# LM335_LTC.net
KiCad netlist of a schematic drawn in EAGLE
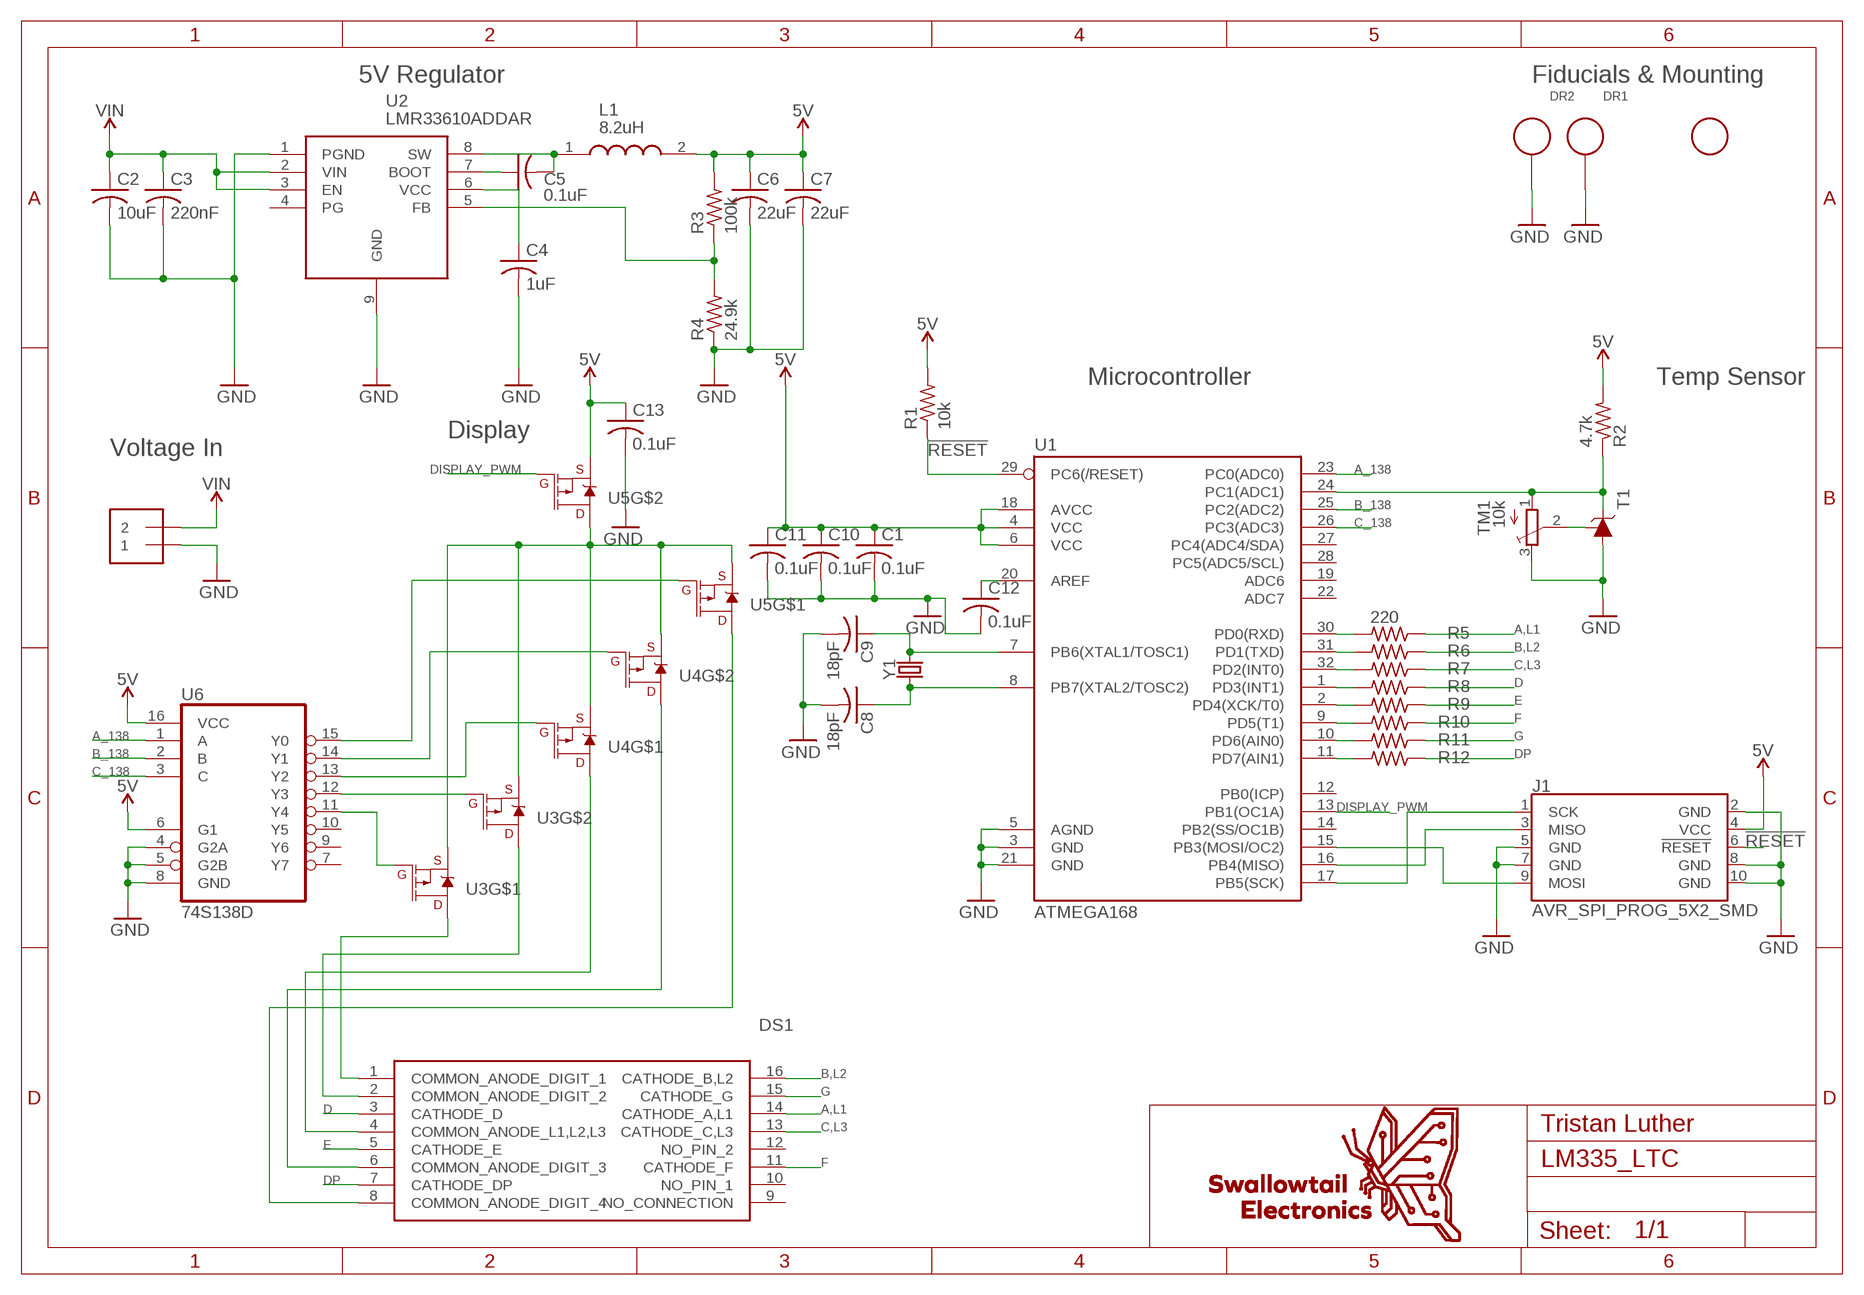
[diagram p0: schematic, sheet 1]

(export (version "E")
  (design (tool "Eeschema 10.0.6"))
  (components
    (comp (ref "C1")
      (value "0.1uF")
      (footprint "eagle-import:C0805")
      (libsource (lib "eagle-import") (part "C-USC0805"))
    )
    (comp (ref "C2")
      (value "10uF")
      (footprint "eagle-import:C0805")
      (libsource (lib "eagle-import") (part "C-USC0805"))
    )
    (comp (ref "C3")
      (value "220nF")
      (footprint "eagle-import:C0805")
      (libsource (lib "eagle-import") (part "C-USC0805"))
    )
    (comp (ref "C4")
      (value "1uF")
      (footprint "eagle-import:C0805")
      (libsource (lib "eagle-import") (part "C-USC0805"))
    )
    (comp (ref "C5")
      (value "0.1uF")
      (footprint "eagle-import:C0805")
      (libsource (lib "eagle-import") (part "C-USC0805"))
    )
    (comp (ref "C6")
      (value "22uF")
      (footprint "eagle-import:C0805")
      (libsource (lib "eagle-import") (part "C-USC0805"))
    )
    (comp (ref "C7")
      (value "22uF")
      (footprint "eagle-import:C0805")
      (libsource (lib "eagle-import") (part "C-USC0805"))
    )
    (comp (ref "C8")
      (value "18pF")
      (footprint "eagle-import:C0805")
      (libsource (lib "eagle-import") (part "C-USC0805"))
    )
    (comp (ref "C9")
      (value "18pF")
      (footprint "eagle-import:C0805")
      (libsource (lib "eagle-import") (part "C-USC0805"))
    )
    (comp (ref "C10")
      (value "0.1uF")
      (footprint "eagle-import:C0805")
      (libsource (lib "eagle-import") (part "C-USC0805"))
    )
    (comp (ref "C11")
      (value "0.1uF")
      (footprint "eagle-import:C0805")
      (libsource (lib "eagle-import") (part "C-USC0805"))
    )
    (comp (ref "C12")
      (value "0.1uF")
      (footprint "eagle-import:C0805")
      (libsource (lib "eagle-import") (part "C-USC0805"))
    )
    (comp (ref "C13")
      (value "0.1uF")
      (footprint "eagle-import:C0805")
      (libsource (lib "eagle-import") (part "C-USC0805"))
    )
    (comp (ref "DR1")
      (value "3MM_DRILL_GND")
      (footprint "eagle-import:3MM_DRILL_GND")
      (libsource (lib "eagle-import") (part "3MM_DRILL_GND"))
    )
    (comp (ref "DR2")
      (value "3MM_DRILL_GND")
      (footprint "eagle-import:3MM_DRILL_GND")
      (libsource (lib "eagle-import") (part "3MM_DRILL_GND"))
    )
    (comp (ref "DS1")
      (value "LTC-4627WC")
      (footprint "eagle-import:DIPS1016W50P254L4018H725Q16N")
      (fields (field (name "MOUSER_PART_NUMBER") "859-LTC-4627WC"))
      (libsource (lib "eagle-import") (part "LTC-4627WC"))
    )
    (comp (ref "J1")
      (value "AVR_SPI_PROG_5X2_SMD")
      (footprint "eagle-import:SAMTECH_FTSH-105-01")
      (libsource (lib "eagle-import") (part "AVR_SPI_PROG_5X2_SMD"))
    )
    (comp (ref "L1")
      (value "8.2uH")
      (footprint "eagle-import:INDPM5752X150N")
      (fields
        (field (name "ARROW_PART_NUMBER") "SRP5015TA-2R2M")
        (field (name "MOUSER_PART_NUMBER") "652-SRP5015TA-2R2M")
      )
      (libsource (lib "eagle-import") (part "SRP5015TA-2R2M"))
    )
    (comp (ref "R1")
      (value "10k")
      (footprint "eagle-import:R0805")
      (libsource (lib "eagle-import") (part "R-US_R0805"))
    )
    (comp (ref "R2")
      (value "4.7k")
      (footprint "eagle-import:R0805")
      (libsource (lib "eagle-import") (part "R-US_R0805"))
    )
    (comp (ref "R3")
      (value "100k")
      (footprint "eagle-import:R0805")
      (libsource (lib "eagle-import") (part "R-US_R0805"))
    )
    (comp (ref "R4")
      (value "24.9k")
      (footprint "eagle-import:R0805")
      (libsource (lib "eagle-import") (part "R-US_R0805"))
    )
    (comp (ref "R5")
      (value "220")
      (footprint "eagle-import:R0805")
      (libsource (lib "eagle-import") (part "R-US_R0805"))
    )
    (comp (ref "R6")
      (value "220")
      (footprint "eagle-import:R0805")
      (libsource (lib "eagle-import") (part "R-US_R0805"))
    )
    (comp (ref "R7")
      (value "220")
      (footprint "eagle-import:R0805")
      (libsource (lib "eagle-import") (part "R-US_R0805"))
    )
    (comp (ref "R8")
      (value "220")
      (footprint "eagle-import:R0805")
      (libsource (lib "eagle-import") (part "R-US_R0805"))
    )
    (comp (ref "R9")
      (value "220")
      (footprint "eagle-import:R0805")
      (libsource (lib "eagle-import") (part "R-US_R0805"))
    )
    (comp (ref "R10")
      (value "220")
      (footprint "eagle-import:R0805")
      (libsource (lib "eagle-import") (part "R-US_R0805"))
    )
    (comp (ref "R11")
      (value "220")
      (footprint "eagle-import:R0805")
      (libsource (lib "eagle-import") (part "R-US_R0805"))
    )
    (comp (ref "R12")
      (value "220")
      (footprint "eagle-import:R0805")
      (libsource (lib "eagle-import") (part "R-US_R0805"))
    )
    (comp (ref "T1")
      (value "LM335")
      (footprint "eagle-import:TO92")
      (libsource (lib "eagle-import") (part "LM335"))
    )
    (comp (ref "TM1")
      (value "10k")
      (footprint "eagle-import:TC33X")
      (libsource (lib "eagle-import") (part "TRIMPOTTC33X"))
    )
    (comp (ref "U$2")
      (value "25-B200-02")
      (footprint "eagle-import:25−B200-02")
      (libsource (lib "eagle-import") (part "25-B200-02"))
    )
    (comp (ref "U$4")
      (value "FIDUCIAL")
      (footprint "eagle-import:FIDUCIAL_1MM")
      (libsource (lib "eagle-import") (part "FIDUCIAL"))
    )
    (comp (ref "U1")
      (value "ATMEGA168")
      (footprint "eagle-import:TQFP32-08")
      (libsource (lib "eagle-import") (part "ATMEGA168"))
    )
    (comp (ref "U2")
      (value "LMR33610ADDAR")
      (footprint "eagle-import:SOIC127P600X170-9N")
      (fields
        (field (name "ARROW_PART_NUMBER") "LMR33630ADDAR")
        (field (name "MOUSER_PART_NUMBER") "595-LMR33630ADDAR")
      )
      (libsource (lib "eagle-import") (part "LMR33610ADDAR"))
    )
    (comp (ref "U3")
      (value "SI1967DH-T1-E3")
      (footprint "eagle-import:SOT363_PHILIPS")
      (libsource (lib "eagle-import") (part "SI1967DH-T1-E3"))
    )
    (comp (ref "U4")
      (value "SI1967DH-T1-E3")
      (footprint "eagle-import:SOT363_PHILIPS")
      (libsource (lib "eagle-import") (part "SI1967DH-T1-E3"))
    )
    (comp (ref "U5")
      (value "SI1967DH-T1-E3")
      (footprint "eagle-import:SOT363_PHILIPS")
      (libsource (lib "eagle-import") (part "SI1967DH-T1-E3"))
    )
    (comp (ref "U6")
      (value "74S138D")
      (footprint "eagle-import:SO16")
      (libsource (lib "eagle-import") (part "74138DS"))
    )
    (comp (ref "Y1")
      (value "16MHz")
      (footprint "eagle-import:CRYSTAL-SMD-5X3.2-4PAD")
      (libsource (lib "eagle-import") (part "CRYSTAL-16MHZSMD-5X3.2"))
    )
  )
  (nets
    (net (code "1") (name "/A,L1") (class "Default")
      (node (ref "DS1") (pin "14") (pinfunction "CATHODE_A,L1_14") (pintype "bidirectional"))
      (node (ref "R5") (pin "1") (pinfunction "1_1") (pintype "passive"))
    )
    (net (code "2") (name "/A_138") (class "Default")
      (node (ref "U1") (pin "23") (pinfunction "PC0(ADC0)_23") (pintype "bidirectional"))
      (node (ref "U6") (pin "1") (pinfunction "A_1") (pintype "input"))
    )
    (net (code "3") (name "/B,L2") (class "Default")
      (node (ref "DS1") (pin "16") (pinfunction "CATHODE_B,L2_16") (pintype "bidirectional"))
      (node (ref "R6") (pin "1") (pinfunction "1_1") (pintype "passive"))
    )
    (net (code "4") (name "/B_138") (class "Default")
      (node (ref "U1") (pin "25") (pinfunction "PC2(ADC2)_25") (pintype "bidirectional"))
      (node (ref "U6") (pin "2") (pinfunction "B_2") (pintype "input"))
    )
    (net (code "5") (name "/C,L3") (class "Default")
      (node (ref "DS1") (pin "13") (pinfunction "CATHODE_C,L3_13") (pintype "bidirectional"))
      (node (ref "R7") (pin "1") (pinfunction "1_1") (pintype "passive"))
    )
    (net (code "6") (name "/C_138") (class "Default")
      (node (ref "U1") (pin "26") (pinfunction "PC3(ADC3)_26") (pintype "bidirectional"))
      (node (ref "U6") (pin "3") (pinfunction "C_3") (pintype "input"))
    )
    (net (code "7") (name "/D") (class "Default")
      (node (ref "DS1") (pin "3") (pinfunction "CATHODE_D_3") (pintype "bidirectional"))
      (node (ref "R8") (pin "1") (pinfunction "1_1") (pintype "passive"))
    )
    (net (code "8") (name "/DISPLAY_PWM") (class "Default")
      (node (ref "U1") (pin "13") (pinfunction "PB1(OC1A)_13") (pintype "bidirectional"))
      (node (ref "U5") (pin "5") (pinfunction "G_5") (pintype "bidirectional"))
    )
    (net (code "9") (name "/DP") (class "Default")
      (node (ref "DS1") (pin "7") (pinfunction "CATHODE_DP_7") (pintype "bidirectional"))
      (node (ref "R12") (pin "1") (pinfunction "1_1") (pintype "passive"))
    )
    (net (code "10") (name "/E") (class "Default")
      (node (ref "DS1") (pin "5") (pinfunction "CATHODE_E_5") (pintype "bidirectional"))
      (node (ref "R9") (pin "1") (pinfunction "1_1") (pintype "passive"))
    )
    (net (code "11") (name "/F") (class "Default")
      (node (ref "DS1") (pin "11") (pinfunction "CATHODE_F_11") (pintype "bidirectional"))
      (node (ref "R10") (pin "1") (pinfunction "1_1") (pintype "passive"))
    )
    (net (code "12") (name "/G") (class "Default")
      (node (ref "DS1") (pin "15") (pinfunction "CATHODE_G_15") (pintype "bidirectional"))
      (node (ref "R11") (pin "1") (pinfunction "1_1") (pintype "passive"))
    )
    (net (code "13") (name "/~{RESET}") (class "Default")
      (node (ref "J1") (pin "6") (pinfunction "~{RESET}_6") (pintype "bidirectional"))
      (node (ref "R1") (pin "1") (pinfunction "1_1") (pintype "passive"))
      (node (ref "U1") (pin "29") (pinfunction "PC6(/RESET)_29") (pintype "bidirectional"))
    )
    (net (code "14") (name "5V") (class "Default")
      (node (ref "C1") (pin "1") (pinfunction "1_1") (pintype "passive"))
      (node (ref "C10") (pin "1") (pinfunction "1_1") (pintype "passive"))
      (node (ref "C11") (pin "1") (pinfunction "1_1") (pintype "passive"))
      (node (ref "C13") (pin "1") (pinfunction "1_1") (pintype "passive"))
      (node (ref "C6") (pin "1") (pinfunction "1_1") (pintype "passive"))
      (node (ref "C7") (pin "1") (pinfunction "1_1") (pintype "passive"))
      (node (ref "J1") (pin "4") (pinfunction "VCC_4") (pintype "bidirectional"))
      (node (ref "L1") (pin "2") (pinfunction "2_2") (pintype "bidirectional"))
      (node (ref "R1") (pin "2") (pinfunction "2_2") (pintype "passive"))
      (node (ref "R2") (pin "2") (pinfunction "2_2") (pintype "passive"))
      (node (ref "R3") (pin "2") (pinfunction "2_2") (pintype "passive"))
      (node (ref "U1") (pin "18") (pinfunction "AVCC_18") (pintype "bidirectional"))
      (node (ref "U1") (pin "4") (pinfunction "VCC_4") (pintype "bidirectional"))
      (node (ref "U1") (pin "6") (pinfunction "VCC_6") (pintype "bidirectional"))
      (node (ref "U5") (pin "4") (pinfunction "S_4") (pintype "bidirectional"))
      (node (ref "U6") (pin "16") (pinfunction "VCC_16") (pintype "power_in"))
      (node (ref "U6") (pin "6") (pinfunction "G1_6") (pintype "input"))
    )
    (net (code "15") (name "GND") (class "Default")
      (node (ref "C1") (pin "2") (pinfunction "2_2") (pintype "passive"))
      (node (ref "C10") (pin "2") (pinfunction "2_2") (pintype "passive"))
      (node (ref "C11") (pin "2") (pinfunction "2_2") (pintype "passive"))
      (node (ref "C12") (pin "2") (pinfunction "2_2") (pintype "passive"))
      (node (ref "C13") (pin "2") (pinfunction "2_2") (pintype "passive"))
      (node (ref "C2") (pin "2") (pinfunction "2_2") (pintype "passive"))
      (node (ref "C3") (pin "2") (pinfunction "2_2") (pintype "passive"))
      (node (ref "C4") (pin "2") (pinfunction "2_2") (pintype "passive"))
      (node (ref "C6") (pin "2") (pinfunction "2_2") (pintype "passive"))
      (node (ref "C7") (pin "2") (pinfunction "2_2") (pintype "passive"))
      (node (ref "C8") (pin "2") (pinfunction "2_2") (pintype "passive"))
      (node (ref "C9") (pin "2") (pinfunction "2_2") (pintype "passive"))
      (node (ref "DR1") (pin "DR") (pinfunction "D$1_DR") (pintype "bidirectional"))
      (node (ref "DR2") (pin "DR") (pinfunction "D$1_DR") (pintype "bidirectional"))
      (node (ref "J1") (pin "10") (pinfunction "GND_10") (pintype "bidirectional"))
      (node (ref "J1") (pin "2") (pinfunction "GND_2") (pintype "bidirectional"))
      (node (ref "J1") (pin "5") (pinfunction "GND_5") (pintype "bidirectional"))
      (node (ref "J1") (pin "7") (pinfunction "GND_7") (pintype "bidirectional"))
      (node (ref "J1") (pin "8") (pinfunction "GND_8") (pintype "bidirectional"))
      (node (ref "R4") (pin "1") (pinfunction "1_1") (pintype "passive"))
      (node (ref "T1") (pin "2") (pinfunction "A_2") (pintype "passive"))
      (node (ref "TM1") (pin "3") (pinfunction "E_3") (pintype "passive"))
      (node (ref "U$2") (pin "P1") (pinfunction "1_P1") (pintype "passive"))
      (node (ref "U1") (pin "21") (pinfunction "GND_21") (pintype "bidirectional"))
      (node (ref "U1") (pin "3") (pinfunction "GND_3") (pintype "bidirectional"))
      (node (ref "U1") (pin "5") (pinfunction "AGND_5") (pintype "bidirectional"))
      (node (ref "U2") (pin "1") (pinfunction "PGND_1") (pintype "bidirectional"))
      (node (ref "U2") (pin "9") (pinfunction "GND_9") (pintype "bidirectional"))
      (node (ref "U6") (pin "4") (pinfunction "G2A_4") (pintype "input"))
      (node (ref "U6") (pin "5") (pinfunction "G2B_5") (pintype "input"))
      (node (ref "U6") (pin "8") (pinfunction "GND_8") (pintype "power_in"))
    )
    (net (code "16") (name "Net-(DS1-COMMON_ANODE_DIGIT_1)") (class "Default")
      (node (ref "DS1") (pin "1") (pinfunction "COMMON_ANODE_DIGIT_1_1") (pintype "bidirectional"))
      (node (ref "U3") (pin "6") (pinfunction "D_6") (pintype "bidirectional"))
    )
    (net (code "17") (name "Net-(DS1-COMMON_ANODE_DIGIT_2)") (class "Default")
      (node (ref "DS1") (pin "2") (pinfunction "COMMON_ANODE_DIGIT_2_2") (pintype "bidirectional"))
      (node (ref "U3") (pin "3") (pinfunction "D_3") (pintype "bidirectional"))
    )
    (net (code "18") (name "Net-(DS1-COMMON_ANODE_DIGIT_3)") (class "Default")
      (node (ref "DS1") (pin "6") (pinfunction "COMMON_ANODE_DIGIT_3_6") (pintype "bidirectional"))
      (node (ref "U4") (pin "3") (pinfunction "D_3") (pintype "bidirectional"))
    )
    (net (code "19") (name "Net-(DS1-COMMON_ANODE_DIGIT_4)") (class "Default")
      (node (ref "DS1") (pin "8") (pinfunction "COMMON_ANODE_DIGIT_4_8") (pintype "bidirectional"))
      (node (ref "U5") (pin "6") (pinfunction "D_6") (pintype "bidirectional"))
    )
    (net (code "20") (name "Net-(DS1-COMMON_ANODE_L1,L2,L3)") (class "Default")
      (node (ref "DS1") (pin "4") (pinfunction "COMMON_ANODE_L1,L2,L3_4") (pintype "bidirectional"))
      (node (ref "U4") (pin "6") (pinfunction "D_6") (pintype "bidirectional"))
    )
    (net (code "21") (name "Net-(J1-MISO)") (class "Default")
      (node (ref "J1") (pin "3") (pinfunction "MISO_3") (pintype "bidirectional"))
      (node (ref "U1") (pin "16") (pinfunction "PB4(MISO)_16") (pintype "bidirectional"))
    )
    (net (code "22") (name "Net-(J1-MOSI)") (class "Default")
      (node (ref "J1") (pin "9") (pinfunction "MOSI_9") (pintype "bidirectional"))
      (node (ref "U1") (pin "15") (pinfunction "PB3(MOSI/OC2)_15") (pintype "bidirectional"))
    )
    (net (code "23") (name "Net-(J1-SCK)") (class "Default")
      (node (ref "J1") (pin "1") (pinfunction "SCK_1") (pintype "bidirectional"))
      (node (ref "U1") (pin "17") (pinfunction "PB5(SCK)_17") (pintype "bidirectional"))
    )
    (net (code "24") (name "Net-(T1-ADJ)") (class "Default")
      (node (ref "T1") (pin "3") (pinfunction "ADJ_3") (pintype "bidirectional"))
      (node (ref "TM1") (pin "2") (pinfunction "S_2") (pintype "passive"))
    )
    (net (code "25") (name "Net-(T1-C)") (class "Default")
      (node (ref "R2") (pin "1") (pinfunction "1_1") (pintype "passive"))
      (node (ref "T1") (pin "1") (pinfunction "C_1") (pintype "passive"))
      (node (ref "TM1") (pin "1") (pinfunction "A_1") (pintype "passive"))
      (node (ref "U1") (pin "24") (pinfunction "PC1(ADC1)_24") (pintype "bidirectional"))
    )
    (net (code "26") (name "Net-(U1-AREF)") (class "Default")
      (node (ref "C12") (pin "1") (pinfunction "1_1") (pintype "passive"))
      (node (ref "U1") (pin "20") (pinfunction "AREF_20") (pintype "bidirectional"))
    )
    (net (code "27") (name "Net-(U1-PB6(XTAL1{slash}TOSC1))") (class "Default")
      (node (ref "C9") (pin "1") (pinfunction "1_1") (pintype "passive"))
      (node (ref "U1") (pin "7") (pinfunction "PB6(XTAL1/TOSC1)_7") (pintype "bidirectional"))
      (node (ref "Y1") (pin "3") (pinfunction "2_3") (pintype "passive"))
    )
    (net (code "28") (name "Net-(U1-PB7(XTAL2{slash}TOSC2))") (class "Default")
      (node (ref "C8") (pin "1") (pinfunction "1_1") (pintype "passive"))
      (node (ref "U1") (pin "8") (pinfunction "PB7(XTAL2/TOSC2)_8") (pintype "bidirectional"))
      (node (ref "Y1") (pin "1") (pinfunction "1_1") (pintype "passive"))
    )
    (net (code "29") (name "Net-(U1-PD0(RXD))") (class "Default")
      (node (ref "R5") (pin "2") (pinfunction "2_2") (pintype "passive"))
      (node (ref "U1") (pin "30") (pinfunction "PD0(RXD)_30") (pintype "bidirectional"))
    )
    (net (code "30") (name "Net-(U1-PD1(TXD))") (class "Default")
      (node (ref "R6") (pin "2") (pinfunction "2_2") (pintype "passive"))
      (node (ref "U1") (pin "31") (pinfunction "PD1(TXD)_31") (pintype "bidirectional"))
    )
    (net (code "31") (name "Net-(U1-PD2(INT0))") (class "Default")
      (node (ref "R7") (pin "2") (pinfunction "2_2") (pintype "passive"))
      (node (ref "U1") (pin "32") (pinfunction "PD2(INT0)_32") (pintype "bidirectional"))
    )
    (net (code "32") (name "Net-(U1-PD3(INT1))") (class "Default")
      (node (ref "R8") (pin "2") (pinfunction "2_2") (pintype "passive"))
      (node (ref "U1") (pin "1") (pinfunction "PD3(INT1)_1") (pintype "bidirectional"))
    )
    (net (code "33") (name "Net-(U1-PD4(XCK{slash}T0))") (class "Default")
      (node (ref "R9") (pin "2") (pinfunction "2_2") (pintype "passive"))
      (node (ref "U1") (pin "2") (pinfunction "PD4(XCK/T0)_2") (pintype "bidirectional"))
    )
    (net (code "34") (name "Net-(U1-PD5(T1))") (class "Default")
      (node (ref "R10") (pin "2") (pinfunction "2_2") (pintype "passive"))
      (node (ref "U1") (pin "9") (pinfunction "PD5(T1)_9") (pintype "bidirectional"))
    )
    (net (code "35") (name "Net-(U1-PD6(AIN0))") (class "Default")
      (node (ref "R11") (pin "2") (pinfunction "2_2") (pintype "passive"))
      (node (ref "U1") (pin "10") (pinfunction "PD6(AIN0)_10") (pintype "bidirectional"))
    )
    (net (code "36") (name "Net-(U1-PD7(AIN1))") (class "Default")
      (node (ref "R12") (pin "2") (pinfunction "2_2") (pintype "passive"))
      (node (ref "U1") (pin "11") (pinfunction "PD7(AIN1)_11") (pintype "bidirectional"))
    )
    (net (code "37") (name "Net-(U2-BOOT)") (class "Default")
      (node (ref "C5") (pin "1") (pinfunction "1_1") (pintype "passive"))
      (node (ref "U2") (pin "7") (pinfunction "BOOT_7") (pintype "bidirectional"))
    )
    (net (code "38") (name "Net-(U2-FB)") (class "Default")
      (node (ref "R3") (pin "1") (pinfunction "1_1") (pintype "passive"))
      (node (ref "R4") (pin "2") (pinfunction "2_2") (pintype "passive"))
      (node (ref "U2") (pin "5") (pinfunction "FB_5") (pintype "bidirectional"))
    )
    (net (code "39") (name "Net-(U2-SW)") (class "Default")
      (node (ref "C5") (pin "2") (pinfunction "2_2") (pintype "passive"))
      (node (ref "L1") (pin "1") (pinfunction "1_1") (pintype "bidirectional"))
      (node (ref "U2") (pin "8") (pinfunction "SW_8") (pintype "bidirectional"))
    )
    (net (code "40") (name "Net-(U2-VCC)") (class "Default")
      (node (ref "C4") (pin "1") (pinfunction "1_1") (pintype "passive"))
      (node (ref "U2") (pin "6") (pinfunction "VCC_6") (pintype "bidirectional"))
    )
    (net (code "41") (name "Net-(U3A-G)") (class "Default")
      (node (ref "U3") (pin "2") (pinfunction "G_2") (pintype "bidirectional"))
      (node (ref "U6") (pin "11") (pinfunction "Y4_11") (pintype "output"))
    )
    (net (code "42") (name "Net-(U3A-S)") (class "Default")
      (node (ref "U3") (pin "1") (pinfunction "S_1") (pintype "bidirectional"))
      (node (ref "U3") (pin "4") (pinfunction "S_4") (pintype "bidirectional"))
      (node (ref "U4") (pin "1") (pinfunction "S_1") (pintype "bidirectional"))
      (node (ref "U4") (pin "4") (pinfunction "S_4") (pintype "bidirectional"))
      (node (ref "U5") (pin "1") (pinfunction "S_1") (pintype "bidirectional"))
      (node (ref "U5") (pin "3") (pinfunction "D_3") (pintype "bidirectional"))
    )
    (net (code "43") (name "Net-(U3B-G)") (class "Default")
      (node (ref "U3") (pin "5") (pinfunction "G_5") (pintype "bidirectional"))
      (node (ref "U6") (pin "12") (pinfunction "Y3_12") (pintype "output"))
    )
    (net (code "44") (name "Net-(U4A-G)") (class "Default")
      (node (ref "U4") (pin "2") (pinfunction "G_2") (pintype "bidirectional"))
      (node (ref "U6") (pin "13") (pinfunction "Y2_13") (pintype "output"))
    )
    (net (code "45") (name "Net-(U4B-G)") (class "Default")
      (node (ref "U4") (pin "5") (pinfunction "G_5") (pintype "bidirectional"))
      (node (ref "U6") (pin "14") (pinfunction "Y1_14") (pintype "output"))
    )
    (net (code "46") (name "Net-(U5A-G)") (class "Default")
      (node (ref "U5") (pin "2") (pinfunction "G_2") (pintype "bidirectional"))
      (node (ref "U6") (pin "15") (pinfunction "Y0_15") (pintype "output"))
    )
    (net (code "47") (name "VIN") (class "Default")
      (node (ref "C2") (pin "1") (pinfunction "1_1") (pintype "passive"))
      (node (ref "C3") (pin "1") (pinfunction "1_1") (pintype "passive"))
      (node (ref "U$2") (pin "P2") (pinfunction "2_P2") (pintype "passive"))
      (node (ref "U2") (pin "2") (pinfunction "VIN_2") (pintype "bidirectional"))
      (node (ref "U2") (pin "3") (pinfunction "EN_3") (pintype "bidirectional"))
    )
    (net (code "48") (name "unconnected-(DS1-NO_CONNECTION-Pad9)") (class "Default")
      (node (ref "DS1") (pin "9") (pinfunction "NO_CONNECTION_9") (pintype "bidirectional"))
    )
    (net (code "49") (name "unconnected-(DS1-NO_PIN_1-Pad10)") (class "Default")
      (node (ref "DS1") (pin "10") (pinfunction "NO_PIN_1_10") (pintype "bidirectional"))
    )
    (net (code "50") (name "unconnected-(DS1-NO_PIN_2-Pad12)") (class "Default")
      (node (ref "DS1") (pin "12") (pinfunction "NO_PIN_2_12") (pintype "bidirectional"))
    )
    (net (code "51") (name "unconnected-(U1-ADC6-Pad19)") (class "Default")
      (node (ref "U1") (pin "19") (pinfunction "ADC6_19") (pintype "bidirectional"))
    )
    (net (code "52") (name "unconnected-(U1-ADC7-Pad22)") (class "Default")
      (node (ref "U1") (pin "22") (pinfunction "ADC7_22") (pintype "bidirectional"))
    )
    (net (code "53") (name "unconnected-(U1-PB0(ICP)-Pad12)") (class "Default")
      (node (ref "U1") (pin "12") (pinfunction "PB0(ICP)_12") (pintype "bidirectional"))
    )
    (net (code "54") (name "unconnected-(U1-PB2(SS{slash}OC1B)-Pad14)") (class "Default")
      (node (ref "U1") (pin "14") (pinfunction "PB2(SS/OC1B)_14") (pintype "bidirectional"))
    )
    (net (code "55") (name "unconnected-(U1-PC4(ADC4{slash}SDA)-Pad27)") (class "Default")
      (node (ref "U1") (pin "27") (pinfunction "PC4(ADC4/SDA)_27") (pintype "bidirectional"))
    )
    (net (code "56") (name "unconnected-(U1-PC5(ADC5{slash}SCL)-Pad28)") (class "Default")
      (node (ref "U1") (pin "28") (pinfunction "PC5(ADC5/SCL)_28") (pintype "bidirectional"))
    )
    (net (code "57") (name "unconnected-(U2-PG-Pad4)") (class "Default")
      (node (ref "U2") (pin "4") (pinfunction "PG_4") (pintype "bidirectional"))
    )
    (net (code "58") (name "unconnected-(U6-Y5-Pad10)") (class "Default")
      (node (ref "U6") (pin "10") (pinfunction "Y5_10") (pintype "output"))
    )
    (net (code "59") (name "unconnected-(U6-Y6-Pad9)") (class "Default")
      (node (ref "U6") (pin "9") (pinfunction "Y6_9") (pintype "output"))
    )
    (net (code "60") (name "unconnected-(U6-Y7-Pad7)") (class "Default")
      (node (ref "U6") (pin "7") (pinfunction "Y7_7") (pintype "output"))
    )
  )
)
